# bottomPCB_f1.net
KiCad netlist of a schematic drawn in EAGLE
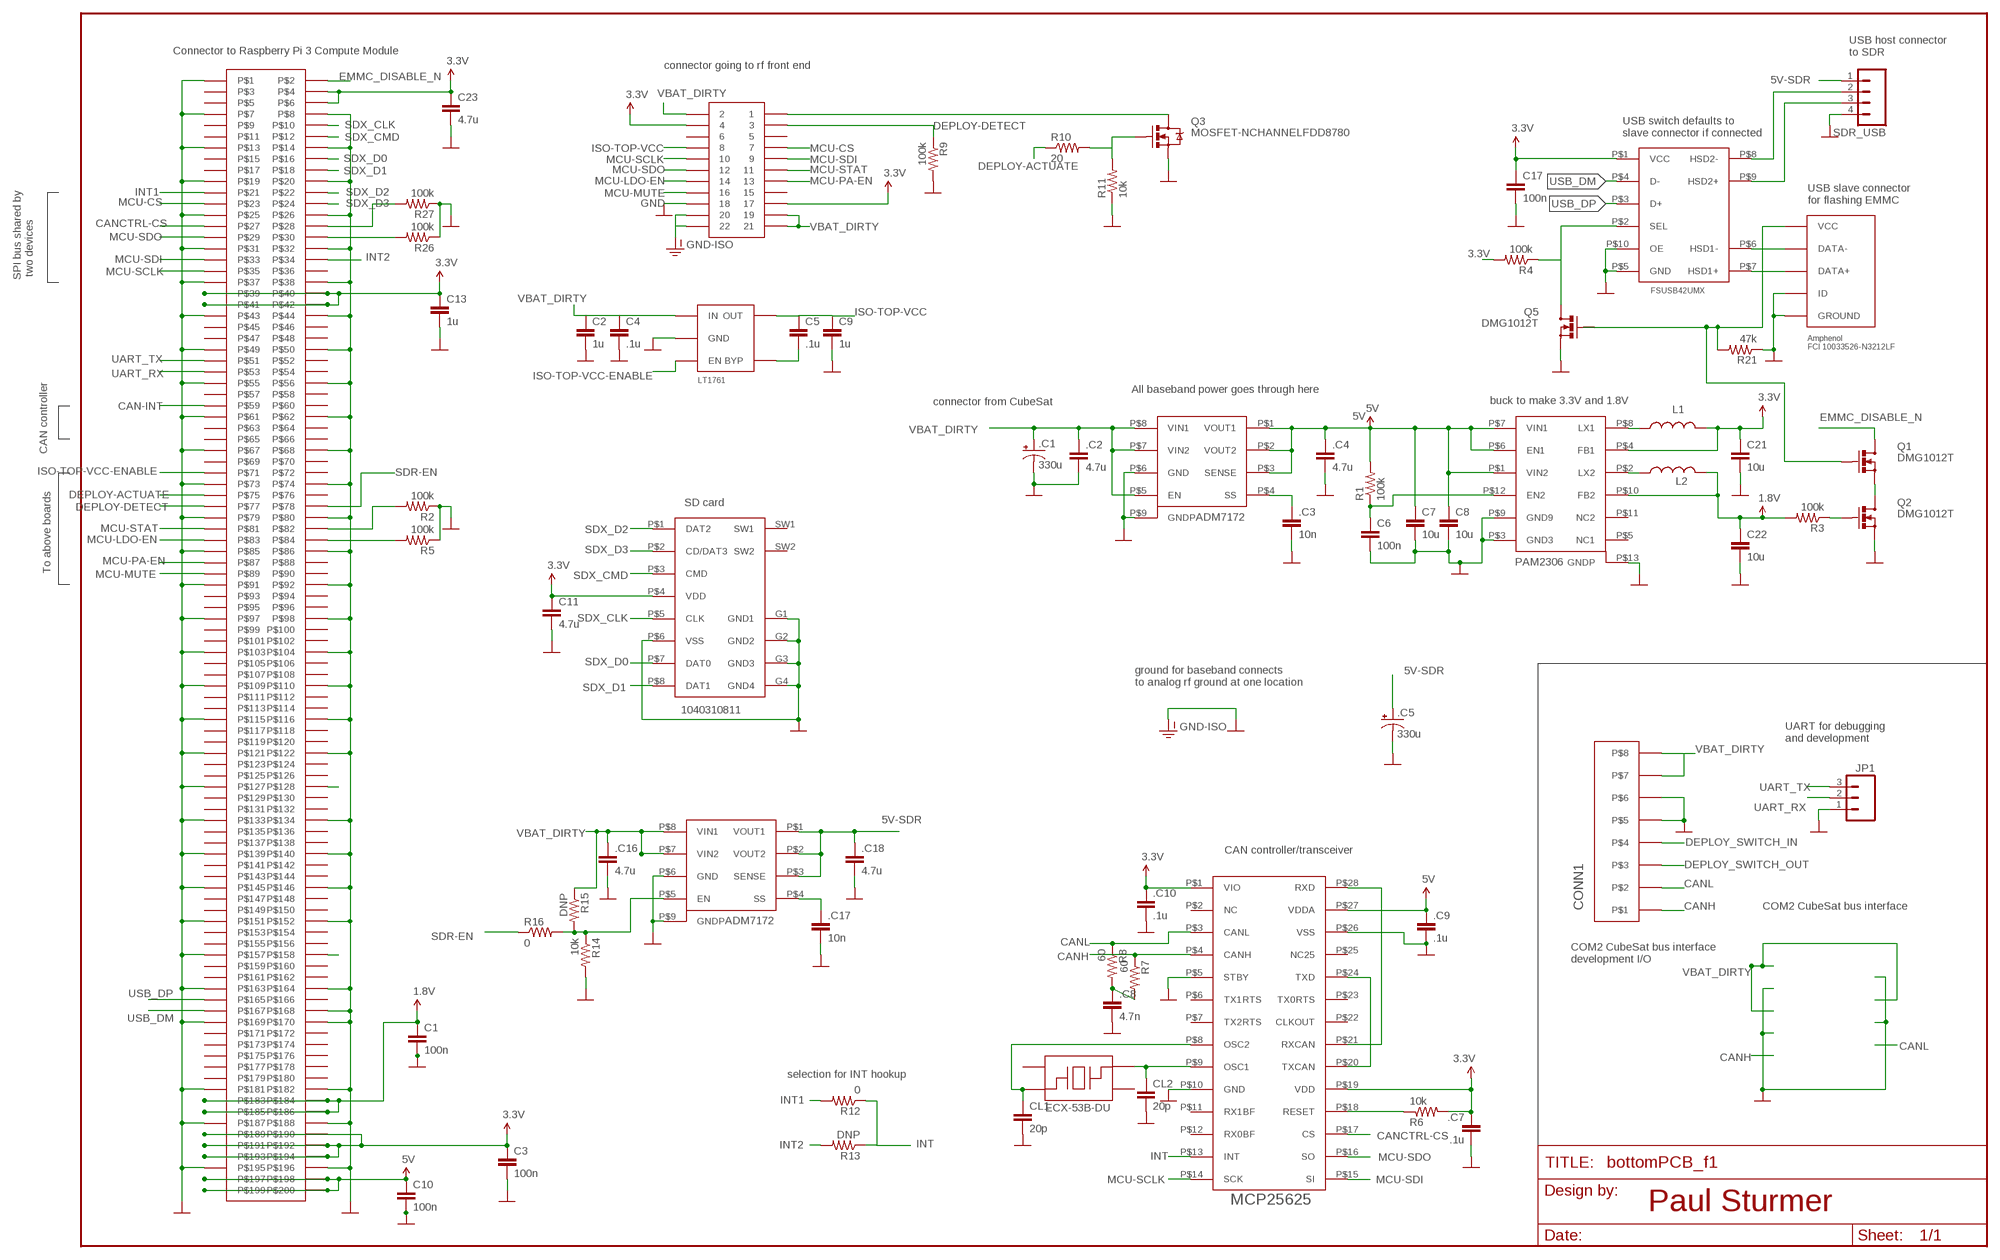
[diagram p0: schematic, sheet 1]

(export (version "E")
  (design (tool "Eeschema 10.0.6"))
  (components
    (comp (ref ".C1")
      (value "330u")
      (footprint "eagle-import:EIA7343")
      (libsource (lib "eagle-import") (part "CAP_POL7343"))
    )
    (comp (ref ".C2")
      (value "4.7u")
      (footprint "eagle-import:1206")
      (libsource (lib "eagle-import") (part "CAP1206"))
    )
    (comp (ref ".C3")
      (value "10n")
      (footprint "eagle-import:0805")
      (libsource (lib "eagle-import") (part "CAP0805"))
    )
    (comp (ref ".C4")
      (value "4.7u")
      (footprint "eagle-import:1206")
      (libsource (lib "eagle-import") (part "CAP1206"))
    )
    (comp (ref ".C5")
      (value "330u")
      (footprint "eagle-import:EIA7343")
      (libsource (lib "eagle-import") (part "CAP_POL7343"))
    )
    (comp (ref ".C7")
      (value ".1u")
      (footprint "eagle-import:0805")
      (libsource (lib "eagle-import") (part "CAP0805"))
    )
    (comp (ref ".C8")
      (value "4.7n")
      (footprint "eagle-import:0805")
      (libsource (lib "eagle-import") (part "CAP0805"))
    )
    (comp (ref ".C9")
      (value ".1u")
      (footprint "eagle-import:0805")
      (libsource (lib "eagle-import") (part "CAP0805"))
    )
    (comp (ref ".C10")
      (value ".1u")
      (footprint "eagle-import:0805")
      (libsource (lib "eagle-import") (part "CAP0805"))
    )
    (comp (ref ".C16")
      (value "4.7u")
      (footprint "eagle-import:1206")
      (libsource (lib "eagle-import") (part "CAP1206"))
    )
    (comp (ref ".C17")
      (value "10n")
      (footprint "eagle-import:0805")
      (libsource (lib "eagle-import") (part "CAP0805"))
    )
    (comp (ref ".C18")
      (value "4.7u")
      (footprint "eagle-import:1206")
      (libsource (lib "eagle-import") (part "CAP1206"))
    )
    (comp (ref "C1")
      (value "100n")
      (footprint "eagle-import:0805")
      (libsource (lib "eagle-import") (part "CAP0805"))
    )
    (comp (ref "C2")
      (value "1u")
      (footprint "eagle-import:0805")
      (libsource (lib "eagle-import") (part "CAP0805"))
    )
    (comp (ref "C3")
      (value "100n")
      (footprint "eagle-import:0805")
      (libsource (lib "eagle-import") (part "CAP0805"))
    )
    (comp (ref "C4")
      (value ".1u")
      (footprint "eagle-import:0805")
      (libsource (lib "eagle-import") (part "CAP0805"))
    )
    (comp (ref "C5")
      (value ".1u")
      (footprint "eagle-import:0805")
      (libsource (lib "eagle-import") (part "CAP0805"))
    )
    (comp (ref "C6")
      (value "100n")
      (footprint "eagle-import:0805")
      (libsource (lib "eagle-import") (part "CAP0805"))
    )
    (comp (ref "C7")
      (value "10u")
      (footprint "eagle-import:1206")
      (libsource (lib "eagle-import") (part "CAP1206"))
    )
    (comp (ref "C8")
      (value "10u")
      (footprint "eagle-import:1206")
      (libsource (lib "eagle-import") (part "CAP1206"))
    )
    (comp (ref "C9")
      (value "1u")
      (footprint "eagle-import:0805")
      (libsource (lib "eagle-import") (part "CAP0805"))
    )
    (comp (ref "C10")
      (value "100n")
      (footprint "eagle-import:0805")
      (libsource (lib "eagle-import") (part "CAP0805"))
    )
    (comp (ref "C11")
      (value "4.7u")
      (footprint "eagle-import:0805")
      (libsource (lib "eagle-import") (part "CAP0805"))
    )
    (comp (ref "C13")
      (value "1u")
      (footprint "eagle-import:0805")
      (libsource (lib "eagle-import") (part "CAP0805"))
    )
    (comp (ref "C17")
      (value "100n")
      (footprint "eagle-import:0805")
      (libsource (lib "eagle-import") (part "CAP0805"))
    )
    (comp (ref "C21")
      (value "10u")
      (footprint "eagle-import:1206")
      (libsource (lib "eagle-import") (part "CAP1206"))
    )
    (comp (ref "C22")
      (value "10u")
      (footprint "eagle-import:1206")
      (libsource (lib "eagle-import") (part "CAP1206"))
    )
    (comp (ref "C23")
      (value "4.7u")
      (footprint "eagle-import:0805")
      (libsource (lib "eagle-import") (part "CAP0805"))
    )
    (comp (ref "CL1")
      (value "20p")
      (footprint "eagle-import:0805")
      (libsource (lib "eagle-import") (part "CAP0805"))
    )
    (comp (ref "CL2")
      (value "20p")
      (footprint "eagle-import:0805")
      (libsource (lib "eagle-import") (part "CAP0805"))
    )
    (comp (ref "CONN1")
      (value "PICOLOCK_8PICOLOCK_8")
      (footprint "eagle-import:PICOLOCK_8")
      (libsource (lib "eagle-import") (part "PICOLOCK_8PICOLOCK_8"))
    )
    (comp (ref "JP1")
      (value "M03LOCK")
      (footprint "eagle-import:1X03_LOCK")
      (libsource (lib "eagle-import") (part "M03LOCK"))
    )
    (comp (ref "L1")
      (value "INDUCTOR_SRN4018")
      (footprint "eagle-import:SDR0403")
      (libsource (lib "eagle-import") (part "INDUCTOR_SRN4018"))
    )
    (comp (ref "L2")
      (value "INDUCTOR_SRN4018")
      (footprint "eagle-import:SDR0403")
      (libsource (lib "eagle-import") (part "INDUCTOR_SRN4018"))
    )
    (comp (ref "Q1")
      (value "DMG1012T")
      (footprint "eagle-import:SOT523")
      (libsource (lib "eagle-import") (part "DMG1012T"))
    )
    (comp (ref "Q2")
      (value "DMG1012T")
      (footprint "eagle-import:SOT523")
      (libsource (lib "eagle-import") (part "DMG1012T"))
    )
    (comp (ref "Q3")
      (value "MOSFET-NCHANNELFDD8780")
      (footprint "eagle-import:DPAK")
      (libsource (lib "eagle-import") (part "MOSFET-NCHANNELFDD8780"))
    )
    (comp (ref "Q5")
      (value "DMG1012T")
      (footprint "eagle-import:SOT523")
      (libsource (lib "eagle-import") (part "DMG1012T"))
    )
    (comp (ref "R1")
      (value "100k")
      (footprint "eagle-import:0805")
      (libsource (lib "eagle-import") (part "RESISTOR0805-RES"))
    )
    (comp (ref "R2")
      (value "100k")
      (footprint "eagle-import:0805")
      (libsource (lib "eagle-import") (part "RESISTOR0805-RES"))
    )
    (comp (ref "R3")
      (value "100k")
      (footprint "eagle-import:0805")
      (libsource (lib "eagle-import") (part "RESISTOR0805-RES"))
    )
    (comp (ref "R4")
      (value "100k")
      (footprint "eagle-import:0805")
      (libsource (lib "eagle-import") (part "RESISTOR0805-RES"))
    )
    (comp (ref "R5")
      (value "100k")
      (footprint "eagle-import:0805")
      (libsource (lib "eagle-import") (part "RESISTOR0805-RES"))
    )
    (comp (ref "R6")
      (value "10k")
      (footprint "eagle-import:0805")
      (libsource (lib "eagle-import") (part "RESISTOR0805-RES"))
    )
    (comp (ref "R7")
      (value "60")
      (footprint "eagle-import:0805")
      (libsource (lib "eagle-import") (part "RESISTOR0805-RES"))
    )
    (comp (ref "R8")
      (value "60")
      (footprint "eagle-import:0805")
      (libsource (lib "eagle-import") (part "RESISTOR0805-RES"))
    )
    (comp (ref "R9")
      (value "100k")
      (footprint "eagle-import:0805")
      (libsource (lib "eagle-import") (part "RESISTOR0805-RES"))
    )
    (comp (ref "R10")
      (value "20")
      (footprint "eagle-import:0805")
      (libsource (lib "eagle-import") (part "RESISTOR0805-RES"))
    )
    (comp (ref "R11")
      (value "10k")
      (footprint "eagle-import:0805")
      (libsource (lib "eagle-import") (part "RESISTOR0805-RES"))
    )
    (comp (ref "R12")
      (value "0")
      (footprint "eagle-import:0805")
      (libsource (lib "eagle-import") (part "RESISTOR0805-RES"))
    )
    (comp (ref "R13")
      (value "DNP")
      (footprint "eagle-import:0805")
      (libsource (lib "eagle-import") (part "RESISTOR0805-RES"))
    )
    (comp (ref "R14")
      (value "10k")
      (footprint "eagle-import:0805")
      (libsource (lib "eagle-import") (part "RESISTOR0805-RES"))
    )
    (comp (ref "R15")
      (value "DNP")
      (footprint "eagle-import:0805")
      (libsource (lib "eagle-import") (part "RESISTOR0805-RES"))
    )
    (comp (ref "R16")
      (value "0")
      (footprint "eagle-import:0805")
      (libsource (lib "eagle-import") (part "RESISTOR0805-RES"))
    )
    (comp (ref "R21")
      (value "47k")
      (footprint "eagle-import:0805")
      (libsource (lib "eagle-import") (part "RESISTOR0805-RES"))
    )
    (comp (ref "R26")
      (value "100k")
      (footprint "eagle-import:0805")
      (libsource (lib "eagle-import") (part "RESISTOR0805-RES"))
    )
    (comp (ref "R27")
      (value "100k")
      (footprint "eagle-import:0805")
      (libsource (lib "eagle-import") (part "RESISTOR0805-RES"))
    )
    (comp (ref "SDR_USB")
      (value "M04LOCK")
      (footprint "eagle-import:1X04_LOCK")
      (libsource (lib "eagle-import") (part "M04LOCK"))
    )
    (comp (ref "U$15")
      (value "USB_MINI-B_AMPHENOL")
      (footprint "eagle-import:USB_MINI_B")
      (libsource (lib "eagle-import") (part "USB_MINI-B_AMPHENOL"))
    )
    (comp (ref "U$16")
      (value "ANALOG_LDO_ADM7172")
      (footprint "eagle-import:8-LFCSP")
      (libsource (lib "eagle-import") (part "ANALOG_LDO_ADM7172"))
    )
    (comp (ref "U$17")
      (value "DIDOESINCORPORATED_BUCK_PAM2306")
      (footprint "eagle-import:WDFN-12L")
      (libsource (lib "eagle-import") (part "DIDOESINCORPORATED_BUCK_PAM2306"))
    )
    (comp (ref "U$18")
      (value "MICROCHIP_CAN_MCP25625_SSOP")
      (footprint "eagle-import:SSOP-28")
      (libsource (lib "eagle-import") (part "MICROCHIP_CAN_MCP25625_SSOP"))
    )
    (comp (ref "U$19")
      (value "FAIRCHILD_USB_FSUSB42UMX")
      (footprint "eagle-import:MSOP_10_LEAD")
      (libsource (lib "eagle-import") (part "FAIRCHILD_USB_FSUSB42UMX"))
    )
    (comp (ref "U$20")
      (value "LINEAR_LDO_LT1761-X")
      (footprint "eagle-import:SOT-23-5")
      (libsource (lib "eagle-import") (part "LINEAR_LDO_LT1761-X"))
    )
    (comp (ref "U$21")
      (value "DDR2_AMPHENOL_10033853-052FSLF")
      (footprint "eagle-import:DDR2")
      (libsource (lib "eagle-import") (part "DDR2_AMPHENOL_10033853-052FSLF"))
    )
    (comp (ref "U$22")
      (value "SD_CARD_1040310811")
      (footprint "eagle-import:SD_CARD_1040310811")
      (libsource (lib "eagle-import") (part "SD_CARD_1040310811"))
    )
    (comp (ref "U$24")
      (value "ECS_CRYSTAL_ECX-53B-DU")
      (footprint "eagle-import:SMD_CRYSTAL")
      (libsource (lib "eagle-import") (part "ECS_CRYSTAL_ECX-53B-DU"))
    )
    (comp (ref "U$26")
      (value "ANALOG_LDO_ADM7172")
      (footprint "eagle-import:8-LFCSP")
      (libsource (lib "eagle-import") (part "ANALOG_LDO_ADM7172"))
    )
    (comp (ref "U$180")
      (value "SSW-111-XX-XXX-D")
      (footprint "eagle-import:SSW-111-XX-XXX-D")
      (libsource (lib "eagle-import") (part "SSW-111-XX-XXX-D"))
    )
  )
  (nets
    (net (code "1") (name "/5V-SDR") (class "Default")
      (node (ref ".C18") (pin "1") (pinfunction "1_1") (pintype "passive"))
      (node (ref ".C5") (pin "A") (pinfunction "+_A") (pintype "passive"))
      (node (ref "SDR_USB") (pin "1") (pinfunction "1_1") (pintype "passive"))
      (node (ref "U$26") (pin "P$1") (pinfunction "VOUT1_P$1") (pintype "bidirectional"))
      (node (ref "U$26") (pin "P$2") (pinfunction "VOUT2_P$2") (pintype "bidirectional"))
      (node (ref "U$26") (pin "P$3") (pinfunction "SENSE_P$3") (pintype "bidirectional"))
    )
    (net (code "2") (name "/CAN-INT") (class "Default")
      (node (ref "U$21") (pin "P$59") (pinfunction "P$59_P$59") (pintype "bidirectional"))
    )
    (net (code "3") (name "/CANCTRL-CS") (class "Default")
      (node (ref "U$18") (pin "P$17") (pinfunction "CS_P$17") (pintype "bidirectional"))
      (node (ref "U$21") (pin "P$27") (pinfunction "P$27_P$27") (pintype "bidirectional"))
    )
    (net (code "4") (name "/CANH") (class "Default")
      (node (ref "CONN1") (pin "P$1") (pinfunction "P$1_P$1") (pintype "bidirectional"))
      (node (ref "R7") (pin "1") (pinfunction "1_1") (pintype "passive"))
      (node (ref "U$18") (pin "P$4") (pinfunction "CANH_P$4") (pintype "bidirectional"))
    )
    (net (code "5") (name "/CANL") (class "Default")
      (node (ref "CONN1") (pin "P$2") (pinfunction "P$2_P$2") (pintype "bidirectional"))
      (node (ref "R8") (pin "1") (pinfunction "1_1") (pintype "passive"))
      (node (ref "U$18") (pin "P$3") (pinfunction "CANL_P$3") (pintype "bidirectional"))
    )
    (net (code "6") (name "/DEPLOY-ACTUATE") (class "Default")
      (node (ref "R10") (pin "1") (pinfunction "1_1") (pintype "passive"))
      (node (ref "U$21") (pin "P$75") (pinfunction "P$75_P$75") (pintype "bidirectional"))
    )
    (net (code "7") (name "/DEPLOY-DETECT") (class "Default")
      (node (ref "R9") (pin "1") (pinfunction "1_1") (pintype "passive"))
      (node (ref "U$180") (pin "3") (pinfunction "3_3") (pintype "bidirectional"))
      (node (ref "U$21") (pin "P$77") (pinfunction "P$77_P$77") (pintype "bidirectional"))
    )
    (net (code "8") (name "/DEPLOY_SWITCH_IN") (class "Default")
      (node (ref "CONN1") (pin "P$4") (pinfunction "P$4_P$4") (pintype "bidirectional"))
    )
    (net (code "9") (name "/DEPLOY_SWITCH_OUT") (class "Default")
      (node (ref "CONN1") (pin "P$3") (pinfunction "P$3_P$3") (pintype "bidirectional"))
    )
    (net (code "10") (name "/EMMC_DISABLE_N") (class "Default")
      (node (ref "Q1") (pin "D") (pinfunction "D_D") (pintype "passive"))
      (node (ref "U$21") (pin "P$2") (pinfunction "P$2_P$2") (pintype "bidirectional"))
    )
    (net (code "11") (name "/INT") (class "Default")
      (node (ref "R12") (pin "1") (pinfunction "1_1") (pintype "passive"))
      (node (ref "R13") (pin "1") (pinfunction "1_1") (pintype "passive"))
      (node (ref "U$18") (pin "P$13") (pinfunction "INT_P$13") (pintype "bidirectional"))
    )
    (net (code "12") (name "/INT1") (class "Default")
      (node (ref "R12") (pin "2") (pinfunction "2_2") (pintype "passive"))
      (node (ref "U$21") (pin "P$21") (pinfunction "P$21_P$21") (pintype "bidirectional"))
    )
    (net (code "13") (name "/INT2") (class "Default")
      (node (ref "R13") (pin "2") (pinfunction "2_2") (pintype "passive"))
      (node (ref "U$21") (pin "P$34") (pinfunction "P$34_P$34") (pintype "bidirectional"))
    )
    (net (code "14") (name "/ISO-TOP-VCC") (class "Default")
      (node (ref "C5") (pin "1") (pinfunction "1_1") (pintype "passive"))
      (node (ref "C9") (pin "1") (pinfunction "1_1") (pintype "passive"))
      (node (ref "U$180") (pin "8") (pinfunction "8_8") (pintype "bidirectional"))
      (node (ref "U$20") (pin "P$5") (pinfunction "OUT_P$5") (pintype "bidirectional"))
    )
    (net (code "15") (name "/ISO-TOP-VCC-ENABLE") (class "Default")
      (node (ref "U$20") (pin "P$3") (pinfunction "EN_P$3") (pintype "bidirectional"))
      (node (ref "U$21") (pin "P$71") (pinfunction "P$71_P$71") (pintype "bidirectional"))
    )
    (net (code "16") (name "/MCU-CS") (class "Default")
      (node (ref "U$180") (pin "7") (pinfunction "7_7") (pintype "bidirectional"))
      (node (ref "U$21") (pin "P$23") (pinfunction "P$23_P$23") (pintype "bidirectional"))
    )
    (net (code "17") (name "/MCU-LDO-EN") (class "Default")
      (node (ref "U$180") (pin "14") (pinfunction "14_14") (pintype "bidirectional"))
      (node (ref "U$21") (pin "P$83") (pinfunction "P$83_P$83") (pintype "bidirectional"))
    )
    (net (code "18") (name "/MCU-MUTE") (class "Default")
      (node (ref "U$180") (pin "16") (pinfunction "16_16") (pintype "bidirectional"))
      (node (ref "U$21") (pin "P$89") (pinfunction "P$89_P$89") (pintype "bidirectional"))
    )
    (net (code "19") (name "/MCU-PA-EN") (class "Default")
      (node (ref "U$180") (pin "13") (pinfunction "13_13") (pintype "bidirectional"))
      (node (ref "U$21") (pin "P$87") (pinfunction "P$87_P$87") (pintype "bidirectional"))
    )
    (net (code "20") (name "/MCU-SCLK") (class "Default")
      (node (ref "U$18") (pin "P$14") (pinfunction "SCK_P$14") (pintype "bidirectional"))
      (node (ref "U$180") (pin "10") (pinfunction "10_10") (pintype "bidirectional"))
      (node (ref "U$21") (pin "P$35") (pinfunction "P$35_P$35") (pintype "bidirectional"))
    )
    (net (code "21") (name "/MCU-SDI") (class "Default")
      (node (ref "U$18") (pin "P$15") (pinfunction "SI_P$15") (pintype "bidirectional"))
      (node (ref "U$180") (pin "9") (pinfunction "9_9") (pintype "bidirectional"))
      (node (ref "U$21") (pin "P$33") (pinfunction "P$33_P$33") (pintype "bidirectional"))
    )
    (net (code "22") (name "/MCU-SDO") (class "Default")
      (node (ref "U$18") (pin "P$16") (pinfunction "SO_P$16") (pintype "bidirectional"))
      (node (ref "U$180") (pin "12") (pinfunction "12_12") (pintype "bidirectional"))
      (node (ref "U$21") (pin "P$29") (pinfunction "P$29_P$29") (pintype "bidirectional"))
    )
    (net (code "23") (name "/MCU-STAT") (class "Default")
      (node (ref "U$180") (pin "11") (pinfunction "11_11") (pintype "bidirectional"))
      (node (ref "U$21") (pin "P$81") (pinfunction "P$81_P$81") (pintype "bidirectional"))
    )
    (net (code "24") (name "/SDR-EN") (class "Default")
      (node (ref "R16") (pin "1") (pinfunction "1_1") (pintype "passive"))
      (node (ref "U$21") (pin "P$78") (pinfunction "P$78_P$78") (pintype "bidirectional"))
    )
    (net (code "25") (name "/SDX_CLK") (class "Default")
      (node (ref "U$21") (pin "P$10") (pinfunction "P$10_P$10") (pintype "bidirectional"))
      (node (ref "U$22") (pin "P$5") (pinfunction "CLK_P$5") (pintype "bidirectional"))
    )
    (net (code "26") (name "/SDX_CMD") (class "Default")
      (node (ref "U$21") (pin "P$12") (pinfunction "P$12_P$12") (pintype "bidirectional"))
      (node (ref "U$22") (pin "P$3") (pinfunction "CMD_P$3") (pintype "bidirectional"))
    )
    (net (code "27") (name "/SDX_D0") (class "Default")
      (node (ref "U$21") (pin "P$16") (pinfunction "P$16_P$16") (pintype "bidirectional"))
      (node (ref "U$22") (pin "P$7") (pinfunction "DAT0_P$7") (pintype "bidirectional"))
    )
    (net (code "28") (name "/SDX_D1") (class "Default")
      (node (ref "U$21") (pin "P$18") (pinfunction "P$18_P$18") (pintype "bidirectional"))
      (node (ref "U$22") (pin "P$8") (pinfunction "DAT1_P$8") (pintype "bidirectional"))
    )
    (net (code "29") (name "/SDX_D2") (class "Default")
      (node (ref "U$21") (pin "P$22") (pinfunction "P$22_P$22") (pintype "bidirectional"))
      (node (ref "U$22") (pin "P$1") (pinfunction "DAT2_P$1") (pintype "bidirectional"))
    )
    (net (code "30") (name "/SDX_D3") (class "Default")
      (node (ref "U$21") (pin "P$24") (pinfunction "P$24_P$24") (pintype "bidirectional"))
      (node (ref "U$22") (pin "P$2") (pinfunction "CD/DAT3_P$2") (pintype "bidirectional"))
    )
    (net (code "31") (name "/UART_RX") (class "Default")
      (node (ref "JP1") (pin "2") (pinfunction "2_2") (pintype "passive"))
      (node (ref "U$21") (pin "P$53") (pinfunction "P$53_P$53") (pintype "bidirectional"))
    )
    (net (code "32") (name "/UART_TX") (class "Default")
      (node (ref "JP1") (pin "3") (pinfunction "3_3") (pintype "passive"))
      (node (ref "U$21") (pin "P$51") (pinfunction "P$51_P$51") (pintype "bidirectional"))
    )
    (net (code "33") (name "/VBAT_DIRTY") (class "Default")
      (node (ref ".C1") (pin "A") (pinfunction "+_A") (pintype "passive"))
      (node (ref ".C16") (pin "1") (pinfunction "1_1") (pintype "passive"))
      (node (ref ".C2") (pin "1") (pinfunction "1_1") (pintype "passive"))
      (node (ref "C2") (pin "1") (pinfunction "1_1") (pintype "passive"))
      (node (ref "C4") (pin "1") (pinfunction "1_1") (pintype "passive"))
      (node (ref "CONN1") (pin "P$7") (pinfunction "P$7_P$7") (pintype "bidirectional"))
      (node (ref "CONN1") (pin "P$8") (pinfunction "P$8_P$8") (pintype "bidirectional"))
      (node (ref "R15") (pin "1") (pinfunction "1_1") (pintype "passive"))
      (node (ref "U$16") (pin "P$5") (pinfunction "EN_P$5") (pintype "bidirectional"))
      (node (ref "U$16") (pin "P$7") (pinfunction "VIN2_P$7") (pintype "bidirectional"))
      (node (ref "U$16") (pin "P$8") (pinfunction "VIN1_P$8") (pintype "bidirectional"))
      (node (ref "U$180") (pin "19") (pinfunction "19_19") (pintype "bidirectional"))
      (node (ref "U$180") (pin "2") (pinfunction "2_2") (pintype "bidirectional"))
      (node (ref "U$180") (pin "21") (pinfunction "21_21") (pintype "bidirectional"))
      (node (ref "U$20") (pin "P$1") (pinfunction "IN_P$1") (pintype "bidirectional"))
      (node (ref "U$26") (pin "P$7") (pinfunction "VIN2_P$7") (pintype "bidirectional"))
      (node (ref "U$26") (pin "P$8") (pinfunction "VIN1_P$8") (pintype "bidirectional"))
    )
    (net (code "34") (name "1.8V") (class "Default")
      (node (ref "C1") (pin "1") (pinfunction "1_1") (pintype "passive"))
      (node (ref "C22") (pin "1") (pinfunction "1_1") (pintype "passive"))
      (node (ref "L2") (pin "P$2") (pinfunction "2_P$2") (pintype "passive"))
      (node (ref "R3") (pin "2") (pinfunction "2_2") (pintype "passive"))
      (node (ref "U$17") (pin "P$10") (pinfunction "FB2_P$10") (pintype "bidirectional"))
      (node (ref "U$21") (pin "P$183") (pinfunction "P$183_P$183") (pintype "bidirectional"))
      (node (ref "U$21") (pin "P$184") (pinfunction "P$184_P$184") (pintype "bidirectional"))
      (node (ref "U$21") (pin "P$185") (pinfunction "P$185_P$185") (pintype "bidirectional"))
      (node (ref "U$21") (pin "P$186") (pinfunction "P$186_P$186") (pintype "bidirectional"))
    )
    (net (code "35") (name "3.3V") (class "Default")
      (node (ref ".C10") (pin "1") (pinfunction "1_1") (pintype "passive"))
      (node (ref ".C7") (pin "1") (pinfunction "1_1") (pintype "passive"))
      (node (ref "C11") (pin "1") (pinfunction "1_1") (pintype "passive"))
      (node (ref "C13") (pin "1") (pinfunction "1_1") (pintype "passive"))
      (node (ref "C17") (pin "1") (pinfunction "1_1") (pintype "passive"))
      (node (ref "C21") (pin "1") (pinfunction "1_1") (pintype "passive"))
      (node (ref "C23") (pin "1") (pinfunction "1_1") (pintype "passive"))
      (node (ref "C3") (pin "1") (pinfunction "1_1") (pintype "passive"))
      (node (ref "L1") (pin "P$2") (pinfunction "2_P$2") (pintype "passive"))
      (node (ref "R4") (pin "2") (pinfunction "2_2") (pintype "passive"))
      (node (ref "R6") (pin "2") (pinfunction "2_2") (pintype "passive"))
      (node (ref "U$17") (pin "P$4") (pinfunction "FB1_P$4") (pintype "bidirectional"))
      (node (ref "U$18") (pin "P$1") (pinfunction "VIO_P$1") (pintype "bidirectional"))
      (node (ref "U$18") (pin "P$19") (pinfunction "VDD_P$19") (pintype "bidirectional"))
      (node (ref "U$180") (pin "17") (pinfunction "17_17") (pintype "bidirectional"))
      (node (ref "U$180") (pin "4") (pinfunction "4_4") (pintype "bidirectional"))
      (node (ref "U$19") (pin "P$1") (pinfunction "VCC_P$1") (pintype "bidirectional"))
      (node (ref "U$21") (pin "P$189") (pinfunction "P$189_P$189") (pintype "bidirectional"))
      (node (ref "U$21") (pin "P$190") (pinfunction "P$190_P$190") (pintype "bidirectional"))
      (node (ref "U$21") (pin "P$191") (pinfunction "P$191_P$191") (pintype "bidirectional"))
      (node (ref "U$21") (pin "P$192") (pinfunction "P$192_P$192") (pintype "bidirectional"))
      (node (ref "U$21") (pin "P$193") (pinfunction "P$193_P$193") (pintype "bidirectional"))
      (node (ref "U$21") (pin "P$194") (pinfunction "P$194_P$194") (pintype "bidirectional"))
      (node (ref "U$21") (pin "P$39") (pinfunction "P$39_P$39") (pintype "bidirectional"))
      (node (ref "U$21") (pin "P$4") (pinfunction "P$4_P$4") (pintype "bidirectional"))
      (node (ref "U$21") (pin "P$40") (pinfunction "P$40_P$40") (pintype "bidirectional"))
      (node (ref "U$21") (pin "P$41") (pinfunction "P$41_P$41") (pintype "bidirectional"))
      (node (ref "U$21") (pin "P$42") (pinfunction "P$42_P$42") (pintype "bidirectional"))
      (node (ref "U$21") (pin "P$6") (pinfunction "P$6_P$6") (pintype "bidirectional"))
      (node (ref "U$22") (pin "P$4") (pinfunction "VDD_P$4") (pintype "bidirectional"))
    )
    (net (code "36") (name "5V") (class "Default")
      (node (ref ".C4") (pin "1") (pinfunction "1_1") (pintype "passive"))
      (node (ref ".C9") (pin "1") (pinfunction "1_1") (pintype "passive"))
      (node (ref "C10") (pin "1") (pinfunction "1_1") (pintype "passive"))
      (node (ref "C7") (pin "1") (pinfunction "1_1") (pintype "passive"))
      (node (ref "C8") (pin "1") (pinfunction "1_1") (pintype "passive"))
      (node (ref "R1") (pin "2") (pinfunction "2_2") (pintype "passive"))
      (node (ref "U$16") (pin "P$1") (pinfunction "VOUT1_P$1") (pintype "bidirectional"))
      (node (ref "U$16") (pin "P$2") (pinfunction "VOUT2_P$2") (pintype "bidirectional"))
      (node (ref "U$16") (pin "P$3") (pinfunction "SENSE_P$3") (pintype "bidirectional"))
      (node (ref "U$17") (pin "P$1") (pinfunction "VIN2_P$1") (pintype "bidirectional"))
      (node (ref "U$17") (pin "P$6") (pinfunction "EN1_P$6") (pintype "bidirectional"))
      (node (ref "U$17") (pin "P$7") (pinfunction "VIN1_P$7") (pintype "bidirectional"))
      (node (ref "U$18") (pin "P$27") (pinfunction "VDDA_P$27") (pintype "bidirectional"))
      (node (ref "U$21") (pin "P$197") (pinfunction "P$197_P$197") (pintype "bidirectional"))
      (node (ref "U$21") (pin "P$198") (pinfunction "P$198_P$198") (pintype "bidirectional"))
      (node (ref "U$21") (pin "P$199") (pinfunction "P$199_P$199") (pintype "bidirectional"))
      (node (ref "U$21") (pin "P$200") (pinfunction "P$200_P$200") (pintype "bidirectional"))
    )
    (net (code "37") (name "DGND") (class "Default")
      (node (ref ".C1") (pin "C") (pinfunction "-_C") (pintype "passive"))
      (node (ref ".C10") (pin "2") (pinfunction "2_2") (pintype "passive"))
      (node (ref ".C16") (pin "2") (pinfunction "2_2") (pintype "passive"))
      (node (ref ".C17") (pin "2") (pinfunction "2_2") (pintype "passive"))
      (node (ref ".C18") (pin "2") (pinfunction "2_2") (pintype "passive"))
      (node (ref ".C2") (pin "2") (pinfunction "2_2") (pintype "passive"))
      (node (ref ".C3") (pin "2") (pinfunction "2_2") (pintype "passive"))
      (node (ref ".C4") (pin "2") (pinfunction "2_2") (pintype "passive"))
      (node (ref ".C5") (pin "C") (pinfunction "-_C") (pintype "passive"))
      (node (ref ".C7") (pin "2") (pinfunction "2_2") (pintype "passive"))
      (node (ref ".C8") (pin "2") (pinfunction "2_2") (pintype "passive"))
      (node (ref ".C9") (pin "2") (pinfunction "2_2") (pintype "passive"))
      (node (ref "C1") (pin "2") (pinfunction "2_2") (pintype "passive"))
      (node (ref "C10") (pin "2") (pinfunction "2_2") (pintype "passive"))
      (node (ref "C11") (pin "2") (pinfunction "2_2") (pintype "passive"))
      (node (ref "C13") (pin "2") (pinfunction "2_2") (pintype "passive"))
      (node (ref "C17") (pin "2") (pinfunction "2_2") (pintype "passive"))
      (node (ref "C2") (pin "2") (pinfunction "2_2") (pintype "passive"))
      (node (ref "C21") (pin "2") (pinfunction "2_2") (pintype "passive"))
      (node (ref "C22") (pin "2") (pinfunction "2_2") (pintype "passive"))
      (node (ref "C23") (pin "2") (pinfunction "2_2") (pintype "passive"))
      (node (ref "C3") (pin "2") (pinfunction "2_2") (pintype "passive"))
      (node (ref "C4") (pin "2") (pinfunction "2_2") (pintype "passive"))
      (node (ref "C6") (pin "2") (pinfunction "2_2") (pintype "passive"))
      (node (ref "C7") (pin "2") (pinfunction "2_2") (pintype "passive"))
      (node (ref "C8") (pin "2") (pinfunction "2_2") (pintype "passive"))
      (node (ref "C9") (pin "2") (pinfunction "2_2") (pintype "passive"))
      (node (ref "CL1") (pin "2") (pinfunction "2_2") (pintype "passive"))
      (node (ref "CL2") (pin "2") (pinfunction "2_2") (pintype "passive"))
      (node (ref "CONN1") (pin "P$5") (pinfunction "P$5_P$5") (pintype "bidirectional"))
      (node (ref "CONN1") (pin "P$6") (pinfunction "P$6_P$6") (pintype "bidirectional"))
      (node (ref "JP1") (pin "1") (pinfunction "1_1") (pintype "passive"))
      (node (ref "Q2") (pin "S") (pinfunction "S_S") (pintype "passive"))
      (node (ref "Q3") (pin "3") (pinfunction "S_3") (pintype "passive"))
      (node (ref "Q5") (pin "S") (pinfunction "S_S") (pintype "passive"))
      (node (ref "R11") (pin "1") (pinfunction "1_1") (pintype "passive"))
      (node (ref "R14") (pin "2") (pinfunction "2_2") (pintype "passive"))
      (node (ref "R2") (pin "1") (pinfunction "1_1") (pintype "passive"))
      (node (ref "R21") (pin "1") (pinfunction "1_1") (pintype "passive"))
      (node (ref "R26") (pin "1") (pinfunction "1_1") (pintype "passive"))
      (node (ref "R27") (pin "1") (pinfunction "1_1") (pintype "passive"))
      (node (ref "R5") (pin "1") (pinfunction "1_1") (pintype "passive"))
      (node (ref "R9") (pin "2") (pinfunction "2_2") (pintype "passive"))
      (node (ref "SDR_USB") (pin "4") (pinfunction "4_4") (pintype "passive"))
      (node (ref "U$15") (pin "GND1") (pinfunction "GROUND_GND1") (pintype "bidirectional"))
      (node (ref "U$15") (pin "GND2") (pinfunction "GROUND_GND2") (pintype "bidirectional"))
      (node (ref "U$15") (pin "GND3") (pinfunction "GROUND_GND3") (pintype "bidirectional"))
      (node (ref "U$15") (pin "GND4") (pinfunction "GROUND_GND4") (pintype "bidirectional"))
      (node (ref "U$15") (pin "GROUND") (pinfunction "GROUND_GROUND") (pintype "bidirectional"))
      (node (ref "U$15") (pin "ID") (pinfunction "ID_ID") (pintype "bidirectional"))
      (node (ref "U$16") (pin "P$6") (pinfunction "GND_P$6") (pintype "bidirectional"))
      (node (ref "U$16") (pin "P$9") (pinfunction "GNDP_P$9") (pintype "bidirectional"))
      (node (ref "U$17") (pin "P$13") (pinfunction "GNDP_P$13") (pintype "bidirectional"))
      (node (ref "U$17") (pin "P$3") (pinfunction "GND3_P$3") (pintype "bidirectional"))
      (node (ref "U$17") (pin "P$9") (pinfunction "GND9_P$9") (pintype "bidirectional"))
      (node (ref "U$18") (pin "P$10") (pinfunction "GND_P$10") (pintype "bidirectional"))
      (node (ref "U$18") (pin "P$26") (pinfunction "VSS_P$26") (pintype "bidirectional"))
      (node (ref "U$18") (pin "P$5") (pinfunction "STBY_P$5") (pintype "bidirectional"))
      (node (ref "U$180") (pin "18") (pinfunction "18_18") (pintype "bidirectional"))
      (node (ref "U$180") (pin "20") (pinfunction "20_20") (pintype "bidirectional"))
      (node (ref "U$180") (pin "22") (pinfunction "22_22") (pintype "bidirectional"))
      (node (ref "U$19") (pin "P$10") (pinfunction "OE_P$10") (pintype "bidirectional"))
      (node (ref "U$19") (pin "P$5") (pinfunction "GND_P$5") (pintype "bidirectional"))
      (node (ref "U$20") (pin "P$2") (pinfunction "GND_P$2") (pintype "bidirectional"))
      (node (ref "U$21") (pin "P$1") (pinfunction "P$1_P$1") (pintype "bidirectional"))
      (node (ref "U$21") (pin "P$103") (pinfunction "P$103_P$103") (pintype "bidirectional"))
      (node (ref "U$21") (pin "P$104") (pinfunction "P$104_P$104") (pintype "bidirectional"))
      (node (ref "U$21") (pin "P$109") (pinfunction "P$109_P$109") (pintype "bidirectional"))
      (node (ref "U$21") (pin "P$110") (pinfunction "P$110_P$110") (pintype "bidirectional"))
      (node (ref "U$21") (pin "P$115") (pinfunction "P$115_P$115") (pintype "bidirectional"))
      (node (ref "U$21") (pin "P$116") (pinfunction "P$116_P$116") (pintype "bidirectional"))
      (node (ref "U$21") (pin "P$121") (pinfunction "P$121_P$121") (pintype "bidirectional"))
      (node (ref "U$21") (pin "P$122") (pinfunction "P$122_P$122") (pintype "bidirectional"))
      (node (ref "U$21") (pin "P$127") (pinfunction "P$127_P$127") (pintype "bidirectional"))
      (node (ref "U$21") (pin "P$13") (pinfunction "P$13_P$13") (pintype "bidirectional"))
      (node (ref "U$21") (pin "P$133") (pinfunction "P$133_P$133") (pintype "bidirectional"))
      (node (ref "U$21") (pin "P$134") (pinfunction "P$134_P$134") (pintype "bidirectional"))
      (node (ref "U$21") (pin "P$139") (pinfunction "P$139_P$139") (pintype "bidirectional"))
      (node (ref "U$21") (pin "P$14") (pinfunction "P$14_P$14") (pintype "bidirectional"))
      (node (ref "U$21") (pin "P$140") (pinfunction "P$140_P$140") (pintype "bidirectional"))
      (node (ref "U$21") (pin "P$145") (pinfunction "P$145_P$145") (pintype "bidirectional"))
      (node (ref "U$21") (pin "P$146") (pinfunction "P$146_P$146") (pintype "bidirectional"))
      (node (ref "U$21") (pin "P$151") (pinfunction "P$151_P$151") (pintype "bidirectional"))
      (node (ref "U$21") (pin "P$152") (pinfunction "P$152_P$152") (pintype "bidirectional"))
      (node (ref "U$21") (pin "P$157") (pinfunction "P$157_P$157") (pintype "bidirectional"))
      (node (ref "U$21") (pin "P$163") (pinfunction "P$163_P$163") (pintype "bidirectional"))
      (node (ref "U$21") (pin "P$164") (pinfunction "P$164_P$164") (pintype "bidirectional"))
      (node (ref "U$21") (pin "P$168") (pinfunction "P$168_P$168") (pintype "bidirectional"))
      (node (ref "U$21") (pin "P$169") (pinfunction "P$169_P$169") (pintype "bidirectional"))
      (node (ref "U$21") (pin "P$170") (pinfunction "P$170_P$170") (pintype "bidirectional"))
      (node (ref "U$21") (pin "P$181") (pinfunction "P$181_P$181") (pintype "bidirectional"))
      (node (ref "U$21") (pin "P$182") (pinfunction "P$182_P$182") (pintype "bidirectional"))
      (node (ref "U$21") (pin "P$187") (pinfunction "P$187_P$187") (pintype "bidirectional"))
      (node (ref "U$21") (pin "P$188") (pinfunction "P$188_P$188") (pintype "bidirectional"))
      (node (ref "U$21") (pin "P$19") (pinfunction "P$19_P$19") (pintype "bidirectional"))
      (node (ref "U$21") (pin "P$195") (pinfunction "P$195_P$195") (pintype "bidirectional"))
      (node (ref "U$21") (pin "P$196") (pinfunction "P$196_P$196") (pintype "bidirectional"))
      (node (ref "U$21") (pin "P$20") (pinfunction "P$20_P$20") (pintype "bidirectional"))
      (node (ref "U$21") (pin "P$25") (pinfunction "P$25_P$25") (pintype "bidirectional"))
      (node (ref "U$21") (pin "P$26") (pinfunction "P$26_P$26") (pintype "bidirectional"))
      (node (ref "U$21") (pin "P$31") (pinfunction "P$31_P$31") (pintype "bidirectional"))
      (node (ref "U$21") (pin "P$32") (pinfunction "P$32_P$32") (pintype "bidirectional"))
      (node (ref "U$21") (pin "P$37") (pinfunction "P$37_P$37") (pintype "bidirectional"))
      (node (ref "U$21") (pin "P$38") (pinfunction "P$38_P$38") (pintype "bidirectional"))
      (node (ref "U$21") (pin "P$43") (pinfunction "P$43_P$43") (pintype "bidirectional"))
      (node (ref "U$21") (pin "P$44") (pinfunction "P$44_P$44") (pintype "bidirectional"))
      (node (ref "U$21") (pin "P$49") (pinfunction "P$49_P$49") (pintype "bidirectional"))
      (node (ref "U$21") (pin "P$50") (pinfunction "P$50_P$50") (pintype "bidirectional"))
      (node (ref "U$21") (pin "P$55") (pinfunction "P$55_P$55") (pintype "bidirectional"))
      (node (ref "U$21") (pin "P$56") (pinfunction "P$56_P$56") (pintype "bidirectional"))
      (node (ref "U$21") (pin "P$61") (pinfunction "P$61_P$61") (pintype "bidirectional"))
      (node (ref "U$21") (pin "P$62") (pinfunction "P$62_P$62") (pintype "bidirectional"))
      (node (ref "U$21") (pin "P$67") (pinfunction "P$67_P$67") (pintype "bidirectional"))
      (node (ref "U$21") (pin "P$68") (pinfunction "P$68_P$68") (pintype "bidirectional"))
      (node (ref "U$21") (pin "P$7") (pinfunction "P$7_P$7") (pintype "bidirectional"))
      (node (ref "U$21") (pin "P$73") (pinfunction "P$73_P$73") (pintype "bidirectional"))
      (node (ref "U$21") (pin "P$74") (pinfunction "P$74_P$74") (pintype "bidirectional"))
      (node (ref "U$21") (pin "P$79") (pinfunction "P$79_P$79") (pintype "bidirectional"))
      (node (ref "U$21") (pin "P$8") (pinfunction "P$8_P$8") (pintype "bidirectional"))
      (node (ref "U$21") (pin "P$80") (pinfunction "P$80_P$80") (pintype "bidirectional"))
      (node (ref "U$21") (pin "P$85") (pinfunction "P$85_P$85") (pintype "bidirectional"))
      (node (ref "U$21") (pin "P$86") (pinfunction "P$86_P$86") (pintype "bidirectional"))
      (node (ref "U$21") (pin "P$91") (pinfunction "P$91_P$91") (pintype "bidirectional"))
      (node (ref "U$21") (pin "P$92") (pinfunction "P$92_P$92") (pintype "bidirectional"))
      (node (ref "U$21") (pin "P$97") (pinfunction "P$97_P$97") (pintype "bidirectional"))
      (node (ref "U$21") (pin "P$98") (pinfunction "P$98_P$98") (pintype "bidirectional"))
      (node (ref "U$22") (pin "G1") (pinfunction "GND1_G1") (pintype "bidirectional"))
      (node (ref "U$22") (pin "G2") (pinfunction "GND2_G2") (pintype "bidirectional"))
      (node (ref "U$22") (pin "G3") (pinfunction "GND3_G3") (pintype "bidirectional"))
      (node (ref "U$22") (pin "G4") (pinfunction "GND4_G4") (pintype "bidirectional"))
      (node (ref "U$22") (pin "P$6") (pinfunction "VSS_P$6") (pintype "bidirectional"))
      (node (ref "U$26") (pin "P$6") (pinfunction "GND_P$6") (pintype "bidirectional"))
      (node (ref "U$26") (pin "P$9") (pinfunction "GNDP_P$9") (pintype "bidirectional"))
    )
    (net (code "38") (name "Net-(.C8-Pad1)") (class "Default")
      (node (ref ".C8") (pin "1") (pinfunction "1_1") (pintype "passive"))
      (node (ref "R7") (pin "2") (pinfunction "2_2") (pintype "passive"))
      (node (ref "R8") (pin "2") (pinfunction "2_2") (pintype "passive"))
    )
    (net (code "39") (name "Net-(L1-1)") (class "Default")
      (node (ref "L1") (pin "P$1") (pinfunction "1_P$1") (pintype "passive"))
      (node (ref "U$17") (pin "P$8") (pinfunction "LX1_P$8") (pintype "bidirectional"))
    )
    (net (code "40") (name "Net-(L2-1)") (class "Default")
      (node (ref "L2") (pin "P$1") (pinfunction "1_P$1") (pintype "passive"))
      (node (ref "U$17") (pin "P$2") (pinfunction "LX2_P$2") (pintype "bidirectional"))
    )
    (net (code "41") (name "Net-(Q1-PadG)") (class "Default")
      (node (ref "Q1") (pin "G") (pinfunction "G_G") (pintype "passive"))
      (node (ref "Q5") (pin "G") (pinfunction "G_G") (pintype "passive"))
      (node (ref "R21") (pin "2") (pinfunction "2_2") (pintype "passive"))
      (node (ref "U$15") (pin "VCC") (pinfunction "VCC_VCC") (pintype "bidirectional"))
    )
    (net (code "42") (name "Net-(Q1-PadS)") (class "Default")
      (node (ref "Q1") (pin "S") (pinfunction "S_S") (pintype "passive"))
      (node (ref "Q2") (pin "D") (pinfunction "D_D") (pintype "passive"))
    )
    (net (code "43") (name "Net-(Q2-PadG)") (class "Default")
      (node (ref "Q2") (pin "G") (pinfunction "G_G") (pintype "passive"))
      (node (ref "R3") (pin "1") (pinfunction "1_1") (pintype "passive"))
    )
    (net (code "44") (name "Net-(Q3-D)") (class "Default")
      (node (ref "Q3") (pin "4") (pinfunction "D_4") (pintype "passive"))
      (node (ref "U$180") (pin "1") (pinfunction "1_1") (pintype "bidirectional"))
    )
    (net (code "45") (name "Net-(Q3-G)") (class "Default")
      (node (ref "Q3") (pin "1") (pinfunction "G_1") (pintype "passive"))
      (node (ref "R10") (pin "2") (pinfunction "2_2") (pintype "passive"))
      (node (ref "R11") (pin "2") (pinfunction "2_2") (pintype "passive"))
    )
    (net (code "46") (name "Net-(R2-Pad2)") (class "Default")
      (node (ref "R2") (pin "2") (pinfunction "2_2") (pintype "passive"))
      (node (ref "U$21") (pin "P$82") (pinfunction "P$82_P$82") (pintype "bidirectional"))
    )
    (net (code "47") (name "Net-(R5-Pad2)") (class "Default")
      (node (ref "R5") (pin "2") (pinfunction "2_2") (pintype "passive"))
      (node (ref "U$21") (pin "P$84") (pinfunction "P$84_P$84") (pintype "bidirectional"))
    )
    (net (code "48") (name "Net-(R26-Pad2)") (class "Default")
      (node (ref "R26") (pin "2") (pinfunction "2_2") (pintype "passive"))
      (node (ref "U$21") (pin "P$30") (pinfunction "P$30_P$30") (pintype "bidirectional"))
    )
    (net (code "49") (name "Net-(R27-Pad2)") (class "Default")
      (node (ref "R27") (pin "2") (pinfunction "2_2") (pintype "passive"))
      (node (ref "U$21") (pin "P$28") (pinfunction "P$28_P$28") (pintype "bidirectional"))
    )
    (net (code "50") (name "Net-(U$16-SS)") (class "Default")
      (node (ref ".C3") (pin "1") (pinfunction "1_1") (pintype "passive"))
      (node (ref "U$16") (pin "P$4") (pinfunction "SS_P$4") (pintype "bidirectional"))
    )
    (net (code "51") (name "Net-(U$17-EN2)") (class "Default")
      (node (ref "C6") (pin "1") (pinfunction "1_1") (pintype "passive"))
      (node (ref "R1") (pin "1") (pinfunction "1_1") (pintype "passive"))
      (node (ref "U$17") (pin "P$12") (pinfunction "EN2_P$12") (pintype "bidirectional"))
    )
    (net (code "52") (name "Net-(U$18-OSC1)") (class "Default")
      (node (ref "CL2") (pin "1") (pinfunction "1_1") (pintype "passive"))
      (node (ref "U$18") (pin "P$9") (pinfunction "OSC1_P$9") (pintype "bidirectional"))
      (node (ref "U$24") (pin "P$3") (pinfunction "P$3_P$3") (pintype "bidirectional"))
    )
    (net (code "53") (name "Net-(U$18-OSC2)") (class "Default")
      (node (ref "CL1") (pin "1") (pinfunction "1_1") (pintype "passive"))
      (node (ref "U$18") (pin "P$8") (pinfunction "OSC2_P$8") (pintype "bidirectional"))
      (node (ref "U$24") (pin "P$1") (pinfunction "P$1_P$1") (pintype "bidirectional"))
    )
    (net (code "54") (name "Net-(U$18-RESET)") (class "Default")
      (node (ref "R6") (pin "1") (pinfunction "1_1") (pintype "passive"))
      (node (ref "U$18") (pin "P$18") (pinfunction "RESET_P$18") (pintype "bidirectional"))
    )
    (net (code "55") (name "Net-(U$18-RXCAN)") (class "Default")
      (node (ref "U$18") (pin "P$21") (pinfunction "RXCAN_P$21") (pintype "bidirectional"))
      (node (ref "U$18") (pin "P$28") (pinfunction "RXD_P$28") (pintype "bidirectional"))
    )
    (net (code "56") (name "Net-(U$18-TXCAN)") (class "Default")
      (node (ref "U$18") (pin "P$20") (pinfunction "TXCAN_P$20") (pintype "bidirectional"))
      (node (ref "U$18") (pin "P$24") (pinfunction "TXD_P$24") (pintype "bidirectional"))
    )
    (net (code "57") (name "Net-(U$19-HSD1+)") (class "Default")
      (node (ref "U$15") (pin "DATA+") (pinfunction "DATA+_DATA+") (pintype "bidirectional"))
      (node (ref "U$19") (pin "P$7") (pinfunction "HSD1+_P$7") (pintype "bidirectional"))
    )
    (net (code "58") (name "Net-(U$19-HSD1-)") (class "Default")
      (node (ref "U$15") (pin "DATA-") (pinfunction "DATA-_DATA-") (pintype "bidirectional"))
      (node (ref "U$19") (pin "P$6") (pinfunction "HSD1-_P$6") (pintype "bidirectional"))
    )
    (net (code "59") (name "Net-(U$19-HSD2+)") (class "Default")
      (node (ref "SDR_USB") (pin "3") (pinfunction "3_3") (pintype "passive"))
      (node (ref "U$19") (pin "P$9") (pinfunction "HSD2+_P$9") (pintype "bidirectional"))
    )
    (net (code "60") (name "Net-(U$19-HSD2-)") (class "Default")
      (node (ref "SDR_USB") (pin "2") (pinfunction "2_2") (pintype "passive"))
      (node (ref "U$19") (pin "P$8") (pinfunction "HSD2-_P$8") (pintype "bidirectional"))
    )
    (net (code "61") (name "Net-(U$19-SEL)") (class "Default")
      (node (ref "Q5") (pin "D") (pinfunction "D_D") (pintype "passive"))
      (node (ref "R4") (pin "1") (pinfunction "1_1") (pintype "passive"))
      (node (ref "U$19") (pin "P$2") (pinfunction "SEL_P$2") (pintype "bidirectional"))
    )
    (net (code "62") (name "Net-(U$20-BYP)") (class "Default")
      (node (ref "C5") (pin "2") (pinfunction "2_2") (pintype "passive"))
      (node (ref "U$20") (pin "P$4") (pinfunction "BYP_P$4") (pintype "bidirectional"))
    )
    (net (code "63") (name "Net-(U$26-EN)") (class "Default")
      (node (ref "R14") (pin "1") (pinfunction "1_1") (pintype "passive"))
      (node (ref "R15") (pin "2") (pinfunction "2_2") (pintype "passive"))
      (node (ref "R16") (pin "2") (pinfunction "2_2") (pintype "passive"))
      (node (ref "U$26") (pin "P$5") (pinfunction "EN_P$5") (pintype "bidirectional"))
    )
    (net (code "64") (name "Net-(U$26-SS)") (class "Default")
      (node (ref ".C17") (pin "1") (pinfunction "1_1") (pintype "passive"))
      (node (ref "U$26") (pin "P$4") (pinfunction "SS_P$4") (pintype "bidirectional"))
    )
    (net (code "65") (name "USB_DM") (class "Default")
      (node (ref "U$19") (pin "P$4") (pinfunction "D-_P$4") (pintype "bidirectional"))
      (node (ref "U$21") (pin "P$167") (pinfunction "P$167_P$167") (pintype "bidirectional"))
    )
    (net (code "66") (name "USB_DP") (class "Default")
      (node (ref "U$19") (pin "P$3") (pinfunction "D+_P$3") (pintype "bidirectional"))
      (node (ref "U$21") (pin "P$165") (pinfunction "P$165_P$165") (pintype "bidirectional"))
    )
    (net (code "67") (name "unconnected-(U$17-NC1-PadP$5)") (class "Default")
      (node (ref "U$17") (pin "P$5") (pinfunction "NC1_P$5") (pintype "bidirectional"))
    )
    (net (code "68") (name "unconnected-(U$17-NC2-PadP$11)") (class "Default")
      (node (ref "U$17") (pin "P$11") (pinfunction "NC2_P$11") (pintype "bidirectional"))
    )
    (net (code "69") (name "unconnected-(U$18-CLKOUT-PadP$22)") (class "Default")
      (node (ref "U$18") (pin "P$22") (pinfunction "CLKOUT_P$22") (pintype "bidirectional"))
    )
    (net (code "70") (name "unconnected-(U$18-NC-PadP$2)") (class "Default")
      (node (ref "U$18") (pin "P$2") (pinfunction "NC_P$2") (pintype "bidirectional"))
    )
    (net (code "71") (name "unconnected-(U$18-NC25-PadP$25)") (class "Default")
      (node (ref "U$18") (pin "P$25") (pinfunction "NC25_P$25") (pintype "bidirectional"))
    )
    (net (code "72") (name "unconnected-(U$18-RX0BF-PadP$12)") (class "Default")
      (node (ref "U$18") (pin "P$12") (pinfunction "RX0BF_P$12") (pintype "bidirectional"))
    )
    (net (code "73") (name "unconnected-(U$18-RX1BF-PadP$11)") (class "Default")
      (node (ref "U$18") (pin "P$11") (pinfunction "RX1BF_P$11") (pintype "bidirectional"))
    )
    (net (code "74") (name "unconnected-(U$18-TX0RTS-PadP$23)") (class "Default")
      (node (ref "U$18") (pin "P$23") (pinfunction "TX0RTS_P$23") (pintype "bidirectional"))
    )
    (net (code "75") (name "unconnected-(U$18-TX1RTS-PadP$6)") (class "Default")
      (node (ref "U$18") (pin "P$6") (pinfunction "TX1RTS_P$6") (pintype "bidirectional"))
    )
    (net (code "76") (name "unconnected-(U$18-TX2RTS-PadP$7)") (class "Default")
      (node (ref "U$18") (pin "P$7") (pinfunction "TX2RTS_P$7") (pintype "bidirectional"))
    )
    (net (code "77") (name "unconnected-(U$21-PadP$3)") (class "Default")
      (node (ref "U$21") (pin "P$3") (pinfunction "P$3_P$3") (pintype "bidirectional"))
    )
    (net (code "78") (name "unconnected-(U$21-PadP$5)") (class "Default")
      (node (ref "U$21") (pin "P$5") (pinfunction "P$5_P$5") (pintype "bidirectional"))
    )
    (net (code "79") (name "unconnected-(U$21-PadP$9)") (class "Default")
      (node (ref "U$21") (pin "P$9") (pinfunction "P$9_P$9") (pintype "bidirectional"))
    )
    (net (code "80") (name "unconnected-(U$21-PadP$11)") (class "Default")
      (node (ref "U$21") (pin "P$11") (pinfunction "P$11_P$11") (pintype "bidirectional"))
    )
    (net (code "81") (name "unconnected-(U$21-PadP$15)") (class "Default")
      (node (ref "U$21") (pin "P$15") (pinfunction "P$15_P$15") (pintype "bidirectional"))
    )
    (net (code "82") (name "unconnected-(U$21-PadP$17)") (class "Default")
      (node (ref "U$21") (pin "P$17") (pinfunction "P$17_P$17") (pintype "bidirectional"))
    )
    (net (code "83") (name "unconnected-(U$21-PadP$36)") (class "Default")
      (node (ref "U$21") (pin "P$36") (pinfunction "P$36_P$36") (pintype "bidirectional"))
    )
    (net (code "84") (name "unconnected-(U$21-PadP$45)") (class "Default")
      (node (ref "U$21") (pin "P$45") (pinfunction "P$45_P$45") (pintype "bidirectional"))
    )
    (net (code "85") (name "unconnected-(U$21-PadP$46)") (class "Default")
      (node (ref "U$21") (pin "P$46") (pinfunction "P$46_P$46") (pintype "bidirectional"))
    )
    (net (code "86") (name "unconnected-(U$21-PadP$47)") (class "Default")
      (node (ref "U$21") (pin "P$47") (pinfunction "P$47_P$47") (pintype "bidirectional"))
    )
    (net (code "87") (name "unconnected-(U$21-PadP$48)") (class "Default")
      (node (ref "U$21") (pin "P$48") (pinfunction "P$48_P$48") (pintype "bidirectional"))
    )
    (net (code "88") (name "unconnected-(U$21-PadP$52)") (class "Default")
      (node (ref "U$21") (pin "P$52") (pinfunction "P$52_P$52") (pintype "bidirectional"))
    )
    (net (code "89") (name "unconnected-(U$21-PadP$54)") (class "Default")
      (node (ref "U$21") (pin "P$54") (pinfunction "P$54_P$54") (pintype "bidirectional"))
    )
    (net (code "90") (name "unconnected-(U$21-PadP$57)") (class "Default")
      (node (ref "U$21") (pin "P$57") (pinfunction "P$57_P$57") (pintype "bidirectional"))
    )
    (net (code "91") (name "unconnected-(U$21-PadP$58)") (class "Default")
      (node (ref "U$21") (pin "P$58") (pinfunction "P$58_P$58") (pintype "bidirectional"))
    )
    (net (code "92") (name "unconnected-(U$21-PadP$60)") (class "Default")
      (node (ref "U$21") (pin "P$60") (pinfunction "P$60_P$60") (pintype "bidirectional"))
    )
    (net (code "93") (name "unconnected-(U$21-PadP$63)") (class "Default")
      (node (ref "U$21") (pin "P$63") (pinfunction "P$63_P$63") (pintype "bidirectional"))
    )
    (net (code "94") (name "unconnected-(U$21-PadP$64)") (class "Default")
      (node (ref "U$21") (pin "P$64") (pinfunction "P$64_P$64") (pintype "bidirectional"))
    )
    (net (code "95") (name "unconnected-(U$21-PadP$65)") (class "Default")
      (node (ref "U$21") (pin "P$65") (pinfunction "P$65_P$65") (pintype "bidirectional"))
    )
    (net (code "96") (name "unconnected-(U$21-PadP$66)") (class "Default")
      (node (ref "U$21") (pin "P$66") (pinfunction "P$66_P$66") (pintype "bidirectional"))
    )
    (net (code "97") (name "unconnected-(U$21-PadP$69)") (class "Default")
      (node (ref "U$21") (pin "P$69") (pinfunction "P$69_P$69") (pintype "bidirectional"))
    )
    (net (code "98") (name "unconnected-(U$21-PadP$70)") (class "Default")
      (node (ref "U$21") (pin "P$70") (pinfunction "P$70_P$70") (pintype "bidirectional"))
    )
    (net (code "99") (name "unconnected-(U$21-PadP$72)") (class "Default")
      (node (ref "U$21") (pin "P$72") (pinfunction "P$72_P$72") (pintype "bidirectional"))
    )
    (net (code "100") (name "unconnected-(U$21-PadP$76)") (class "Default")
      (node (ref "U$21") (pin "P$76") (pinfunction "P$76_P$76") (pintype "bidirectional"))
    )
    (net (code "101") (name "unconnected-(U$21-PadP$88)") (class "Default")
      (node (ref "U$21") (pin "P$88") (pinfunction "P$88_P$88") (pintype "bidirectional"))
    )
    (net (code "102") (name "unconnected-(U$21-PadP$90)") (class "Default")
      (node (ref "U$21") (pin "P$90") (pinfunction "P$90_P$90") (pintype "bidirectional"))
    )
    (net (code "103") (name "unconnected-(U$21-PadP$93)") (class "Default")
      (node (ref "U$21") (pin "P$93") (pinfunction "P$93_P$93") (pintype "bidirectional"))
    )
    (net (code "104") (name "unconnected-(U$21-PadP$94)") (class "Default")
      (node (ref "U$21") (pin "P$94") (pinfunction "P$94_P$94") (pintype "bidirectional"))
    )
    (net (code "105") (name "unconnected-(U$21-PadP$95)") (class "Default")
      (node (ref "U$21") (pin "P$95") (pinfunction "P$95_P$95") (pintype "bidirectional"))
    )
    (net (code "106") (name "unconnected-(U$21-PadP$96)") (class "Default")
      (node (ref "U$21") (pin "P$96") (pinfunction "P$96_P$96") (pintype "bidirectional"))
    )
    (net (code "107") (name "unconnected-(U$21-PadP$99)") (class "Default")
      (node (ref "U$21") (pin "P$99") (pinfunction "P$99_P$99") (pintype "bidirectional"))
    )
    (net (code "108") (name "unconnected-(U$21-PadP$100)") (class "Default")
      (node (ref "U$21") (pin "P$100") (pinfunction "P$100_P$100") (pintype "bidirectional"))
    )
    (net (code "109") (name "unconnected-(U$21-PadP$101)") (class "Default")
      (node (ref "U$21") (pin "P$101") (pinfunction "P$101_P$101") (pintype "bidirectional"))
    )
    (net (code "110") (name "unconnected-(U$21-PadP$102)") (class "Default")
      (node (ref "U$21") (pin "P$102") (pinfunction "P$102_P$102") (pintype "bidirectional"))
    )
    (net (code "111") (name "unconnected-(U$21-PadP$105)") (class "Default")
      (node (ref "U$21") (pin "P$105") (pinfunction "P$105_P$105") (pintype "bidirectional"))
    )
    (net (code "112") (name "unconnected-(U$21-PadP$106)") (class "Default")
      (node (ref "U$21") (pin "P$106") (pinfunction "P$106_P$106") (pintype "bidirectional"))
    )
    (net (code "113") (name "unconnected-(U$21-PadP$107)") (class "Default")
      (node (ref "U$21") (pin "P$107") (pinfunction "P$107_P$107") (pintype "bidirectional"))
    )
    (net (code "114") (name "unconnected-(U$21-PadP$108)") (class "Default")
      (node (ref "U$21") (pin "P$108") (pinfunction "P$108_P$108") (pintype "bidirectional"))
    )
    (net (code "115") (name "unconnected-(U$21-PadP$111)") (class "Default")
      (node (ref "U$21") (pin "P$111") (pinfunction "P$111_P$111") (pintype "bidirectional"))
    )
    (net (code "116") (name "unconnected-(U$21-PadP$112)") (class "Default")
      (node (ref "U$21") (pin "P$112") (pinfunction "P$112_P$112") (pintype "bidirectional"))
    )
    (net (code "117") (name "unconnected-(U$21-PadP$113)") (class "Default")
      (node (ref "U$21") (pin "P$113") (pinfunction "P$113_P$113") (pintype "bidirectional"))
    )
    (net (code "118") (name "unconnected-(U$21-PadP$114)") (class "Default")
      (node (ref "U$21") (pin "P$114") (pinfunction "P$114_P$114") (pintype "bidirectional"))
    )
    (net (code "119") (name "unconnected-(U$21-PadP$117)") (class "Default")
      (node (ref "U$21") (pin "P$117") (pinfunction "P$117_P$117") (pintype "bidirectional"))
    )
    (net (code "120") (name "unconnected-(U$21-PadP$118)") (class "Default")
      (node (ref "U$21") (pin "P$118") (pinfunction "P$118_P$118") (pintype "bidirectional"))
    )
    (net (code "121") (name "unconnected-(U$21-PadP$119)") (class "Default")
      (node (ref "U$21") (pin "P$119") (pinfunction "P$119_P$119") (pintype "bidirectional"))
    )
    (net (code "122") (name "unconnected-(U$21-PadP$120)") (class "Default")
      (node (ref "U$21") (pin "P$120") (pinfunction "P$120_P$120") (pintype "bidirectional"))
    )
    (net (code "123") (name "unconnected-(U$21-PadP$123)") (class "Default")
      (node (ref "U$21") (pin "P$123") (pinfunction "P$123_P$123") (pintype "bidirectional"))
    )
    (net (code "124") (name "unconnected-(U$21-PadP$124)") (class "Default")
      (node (ref "U$21") (pin "P$124") (pinfunction "P$124_P$124") (pintype "bidirectional"))
    )
    (net (code "125") (name "unconnected-(U$21-PadP$125)") (class "Default")
      (node (ref "U$21") (pin "P$125") (pinfunction "P$125_P$125") (pintype "bidirectional"))
    )
    (net (code "126") (name "unconnected-(U$21-PadP$126)") (class "Default")
      (node (ref "U$21") (pin "P$126") (pinfunction "P$126_P$126") (pintype "bidirectional"))
    )
    (net (code "127") (name "unconnected-(U$21-PadP$128)") (class "Default")
      (node (ref "U$21") (pin "P$128") (pinfunction "P$128_P$128") (pintype "bidirectional"))
    )
    (net (code "128") (name "unconnected-(U$21-PadP$129)") (class "Default")
      (node (ref "U$21") (pin "P$129") (pinfunction "P$129_P$129") (pintype "bidirectional"))
    )
    (net (code "129") (name "unconnected-(U$21-PadP$130)") (class "Default")
      (node (ref "U$21") (pin "P$130") (pinfunction "P$130_P$130") (pintype "bidirectional"))
    )
    (net (code "130") (name "unconnected-(U$21-PadP$131)") (class "Default")
      (node (ref "U$21") (pin "P$131") (pinfunction "P$131_P$131") (pintype "bidirectional"))
    )
    (net (code "131") (name "unconnected-(U$21-PadP$132)") (class "Default")
      (node (ref "U$21") (pin "P$132") (pinfunction "P$132_P$132") (pintype "bidirectional"))
    )
    (net (code "132") (name "unconnected-(U$21-PadP$135)") (class "Default")
      (node (ref "U$21") (pin "P$135") (pinfunction "P$135_P$135") (pintype "bidirectional"))
    )
    (net (code "133") (name "unconnected-(U$21-PadP$136)") (class "Default")
      (node (ref "U$21") (pin "P$136") (pinfunction "P$136_P$136") (pintype "bidirectional"))
    )
    (net (code "134") (name "unconnected-(U$21-PadP$137)") (class "Default")
      (node (ref "U$21") (pin "P$137") (pinfunction "P$137_P$137") (pintype "bidirectional"))
    )
    (net (code "135") (name "unconnected-(U$21-PadP$138)") (class "Default")
      (node (ref "U$21") (pin "P$138") (pinfunction "P$138_P$138") (pintype "bidirectional"))
    )
    (net (code "136") (name "unconnected-(U$21-PadP$141)") (class "Default")
      (node (ref "U$21") (pin "P$141") (pinfunction "P$141_P$141") (pintype "bidirectional"))
    )
    (net (code "137") (name "unconnected-(U$21-PadP$142)") (class "Default")
      (node (ref "U$21") (pin "P$142") (pinfunction "P$142_P$142") (pintype "bidirectional"))
    )
    (net (code "138") (name "unconnected-(U$21-PadP$143)") (class "Default")
      (node (ref "U$21") (pin "P$143") (pinfunction "P$143_P$143") (pintype "bidirectional"))
    )
    (net (code "139") (name "unconnected-(U$21-PadP$144)") (class "Default")
      (node (ref "U$21") (pin "P$144") (pinfunction "P$144_P$144") (pintype "bidirectional"))
    )
    (net (code "140") (name "unconnected-(U$21-PadP$147)") (class "Default")
      (node (ref "U$21") (pin "P$147") (pinfunction "P$147_P$147") (pintype "bidirectional"))
    )
    (net (code "141") (name "unconnected-(U$21-PadP$148)") (class "Default")
      (node (ref "U$21") (pin "P$148") (pinfunction "P$148_P$148") (pintype "bidirectional"))
    )
    (net (code "142") (name "unconnected-(U$21-PadP$149)") (class "Default")
      (node (ref "U$21") (pin "P$149") (pinfunction "P$149_P$149") (pintype "bidirectional"))
    )
    (net (code "143") (name "unconnected-(U$21-PadP$150)") (class "Default")
      (node (ref "U$21") (pin "P$150") (pinfunction "P$150_P$150") (pintype "bidirectional"))
    )
    (net (code "144") (name "unconnected-(U$21-PadP$153)") (class "Default")
      (node (ref "U$21") (pin "P$153") (pinfunction "P$153_P$153") (pintype "bidirectional"))
    )
    (net (code "145") (name "unconnected-(U$21-PadP$154)") (class "Default")
      (node (ref "U$21") (pin "P$154") (pinfunction "P$154_P$154") (pintype "bidirectional"))
    )
    (net (code "146") (name "unconnected-(U$21-PadP$155)") (class "Default")
      (node (ref "U$21") (pin "P$155") (pinfunction "P$155_P$155") (pintype "bidirectional"))
    )
    (net (code "147") (name "unconnected-(U$21-PadP$156)") (class "Default")
      (node (ref "U$21") (pin "P$156") (pinfunction "P$156_P$156") (pintype "bidirectional"))
    )
    (net (code "148") (name "unconnected-(U$21-PadP$158)") (class "Default")
      (node (ref "U$21") (pin "P$158") (pinfunction "P$158_P$158") (pintype "bidirectional"))
    )
    (net (code "149") (name "unconnected-(U$21-PadP$159)") (class "Default")
      (node (ref "U$21") (pin "P$159") (pinfunction "P$159_P$159") (pintype "bidirectional"))
    )
    (net (code "150") (name "unconnected-(U$21-PadP$160)") (class "Default")
      (node (ref "U$21") (pin "P$160") (pinfunction "P$160_P$160") (pintype "bidirectional"))
    )
    (net (code "151") (name "unconnected-(U$21-PadP$161)") (class "Default")
      (node (ref "U$21") (pin "P$161") (pinfunction "P$161_P$161") (pintype "bidirectional"))
    )
    (net (code "152") (name "unconnected-(U$21-PadP$162)") (class "Default")
      (node (ref "U$21") (pin "P$162") (pinfunction "P$162_P$162") (pintype "bidirectional"))
    )
    (net (code "153") (name "unconnected-(U$21-PadP$166)") (class "Default")
      (node (ref "U$21") (pin "P$166") (pinfunction "P$166_P$166") (pintype "bidirectional"))
    )
    (net (code "154") (name "unconnected-(U$21-PadP$171)") (class "Default")
      (node (ref "U$21") (pin "P$171") (pinfunction "P$171_P$171") (pintype "bidirectional"))
    )
    (net (code "155") (name "unconnected-(U$21-PadP$172)") (class "Default")
      (node (ref "U$21") (pin "P$172") (pinfunction "P$172_P$172") (pintype "bidirectional"))
    )
    (net (code "156") (name "unconnected-(U$21-PadP$173)") (class "Default")
      (node (ref "U$21") (pin "P$173") (pinfunction "P$173_P$173") (pintype "bidirectional"))
    )
    (net (code "157") (name "unconnected-(U$21-PadP$174)") (class "Default")
      (node (ref "U$21") (pin "P$174") (pinfunction "P$174_P$174") (pintype "bidirectional"))
    )
    (net (code "158") (name "unconnected-(U$21-PadP$175)") (class "Default")
      (node (ref "U$21") (pin "P$175") (pinfunction "P$175_P$175") (pintype "bidirectional"))
    )
    (net (code "159") (name "unconnected-(U$21-PadP$176)") (class "Default")
      (node (ref "U$21") (pin "P$176") (pinfunction "P$176_P$176") (pintype "bidirectional"))
    )
    (net (code "160") (name "unconnected-(U$21-PadP$177)") (class "Default")
      (node (ref "U$21") (pin "P$177") (pinfunction "P$177_P$177") (pintype "bidirectional"))
    )
    (net (code "161") (name "unconnected-(U$21-PadP$178)") (class "Default")
      (node (ref "U$21") (pin "P$178") (pinfunction "P$178_P$178") (pintype "bidirectional"))
    )
    (net (code "162") (name "unconnected-(U$21-PadP$179)") (class "Default")
      (node (ref "U$21") (pin "P$179") (pinfunction "P$179_P$179") (pintype "bidirectional"))
    )
    (net (code "163") (name "unconnected-(U$21-PadP$180)") (class "Default")
      (node (ref "U$21") (pin "P$180") (pinfunction "P$180_P$180") (pintype "bidirectional"))
    )
    (net (code "164") (name "unconnected-(U$22-PadSW1)") (class "Default")
      (node (ref "U$22") (pin "SW1") (pinfunction "SW1_SW1") (pintype "bidirectional"))
    )
    (net (code "165") (name "unconnected-(U$22-PadSW2)") (class "Default")
      (node (ref "U$22") (pin "SW2") (pinfunction "SW2_SW2") (pintype "bidirectional"))
    )
    (net (code "166") (name "unconnected-(U$24-PadP$2)") (class "Default")
      (node (ref "U$24") (pin "P$2") (pinfunction "P$2_P$2") (pintype "bidirectional"))
    )
    (net (code "167") (name "unconnected-(U$24-PadP$4)") (class "Default")
      (node (ref "U$24") (pin "P$4") (pinfunction "P$4_P$4") (pintype "bidirectional"))
    )
    (net (code "168") (name "unconnected-(U$180-Pad5)") (class "Default")
      (node (ref "U$180") (pin "5") (pinfunction "5_5") (pintype "bidirectional"))
    )
    (net (code "169") (name "unconnected-(U$180-Pad6)") (class "Default")
      (node (ref "U$180") (pin "6") (pinfunction "6_6") (pintype "bidirectional"))
    )
    (net (code "170") (name "unconnected-(U$180-Pad15)") (class "Default")
      (node (ref "U$180") (pin "15") (pinfunction "15_15") (pintype "bidirectional"))
    )
  )
)
